# Power.net
KiCad netlist of a schematic drawn in Altium Designer
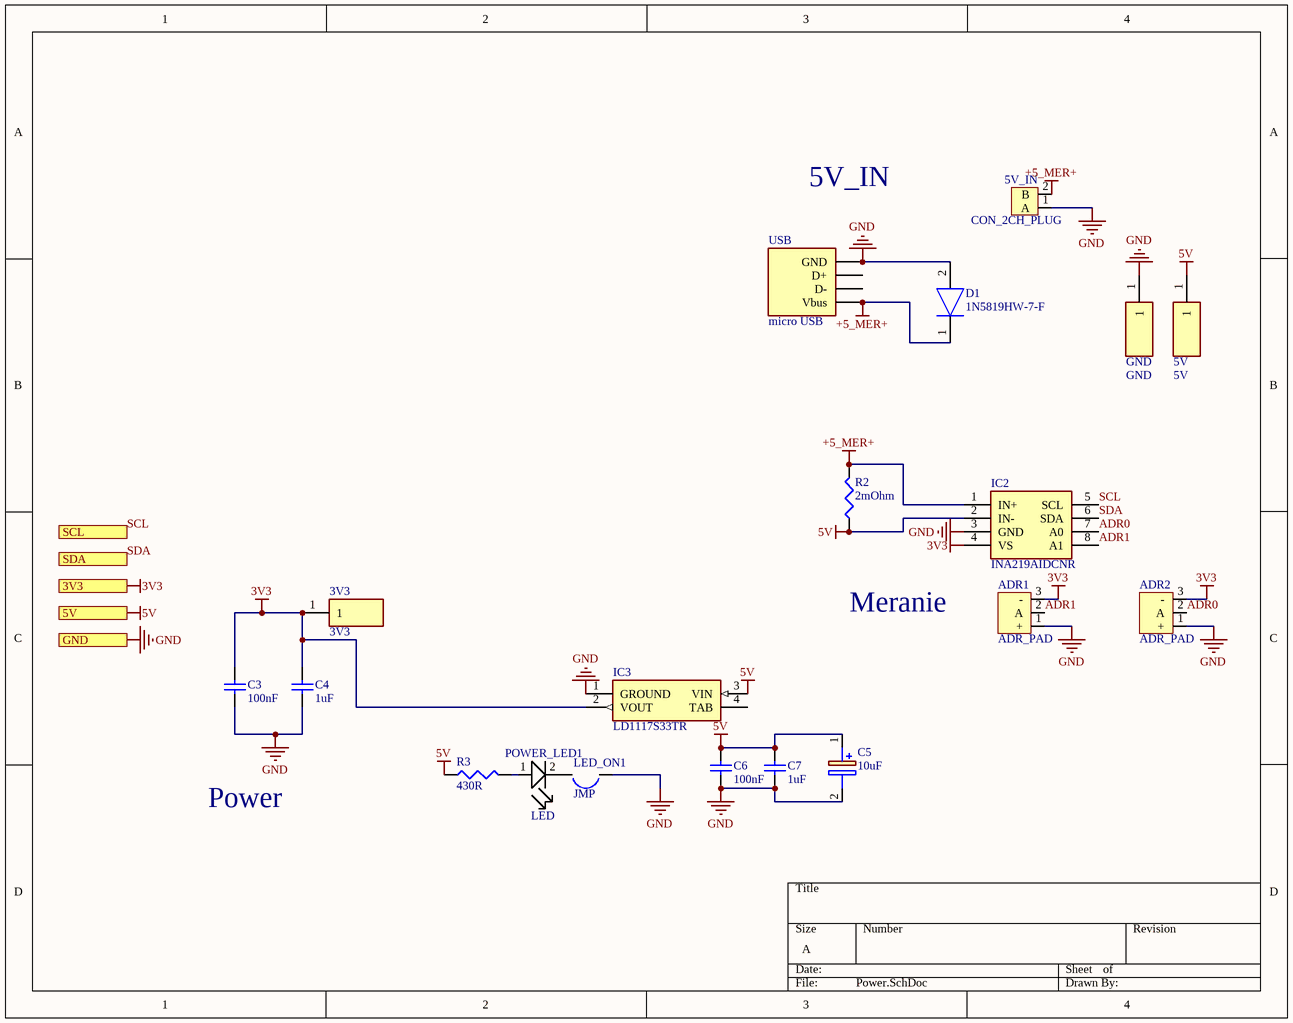
[diagram p0: Power.SchDoc]

(export (version "E")
  (design (tool "Eeschema 10.0.6"))
  (components
    (comp (ref "3V3")
      (value "3V3")
      (footprint "1508000150000030")
      (description "Undefined or Miscellaneous")
      (fields (field (name "MANUFACTURER_PART_NUMBER") "5015") (field (name "MOUSER PART NUMBER") "534-5015"))
      (libsource (lib "*") (part "5015"))
    )
    (comp (ref "5V")
      (value "5V")
      (footprint "1508000150000030")
      (description "Undefined or Miscellaneous")
      (fields (field (name "MANUFACTURER_PART_NUMBER") "5015") (field (name "MOUSER PART NUMBER") "534-5015"))
      (libsource (lib "") (part "5015_1"))
    )
    (comp (ref "5V_IN")
      (value "CON_2CH_PLUG")
      (footprint "CON_2CH_PLUG")
      (description "TBG-5.0-KW-2P")
      (libsource (lib "SCH_Aquatec") (part "CON_2CH_PLUG"))
    )
    (comp (ref "ADR1")
      (value "ADR_PAD")
      (footprint "SOLDER_PAD")
      (description "ADR PAD 3 PIN")
      (libsource (lib "SCH_Aquatec") (part "ADR_PAD"))
    )
    (comp (ref "ADR2")
      (value "ADR_PAD")
      (footprint "SOLDER_PAD")
      (description "ADR PAD 3 PIN")
      (libsource (lib "SCH_Aquatec") (part "ADR_PAD"))
    )
    (comp (ref "C3")
      (value "100nF")
      (footprint "1608[0603]")
      (description "Capacitor")
      (fields (field (name "PUBLISHER") "Altium Limited"))
      (libsource (lib "Miscellaneous Devices") (part "Cap Semi"))
    )
    (comp (ref "C4")
      (value "1uF")
      (footprint "1608[0603]")
      (description "Capacitor")
      (fields (field (name "PUBLISHER") "Altium Limited"))
      (libsource (lib "Miscellaneous Devices") (part "Cap Semi"))
    )
    (comp (ref "C5")
      (value "10uF")
      (footprint "CAPPM3216X180N")
      (description "Capacitor Polarised")
      (fields
        (field (name "MANUFACTURER_PART_NUMBER") "TAJA106K004RNJ")
        (field (name "MOUSER PART NUMBER") "581-TAJA106K004R")
      )
      (libsource (lib "*") (part "TAJA106K004RNJ"))
    )
    (comp (ref "C6")
      (value "100nF")
      (footprint "1608[0603]")
      (description "Capacitor")
      (fields (field (name "PUBLISHER") "Altium Limited"))
      (libsource (lib "Miscellaneous Devices") (part "Cap Semi"))
    )
    (comp (ref "C7")
      (value "1uF")
      (footprint "1608[0603]")
      (description "Capacitor")
      (fields (field (name "PUBLISHER") "Altium Limited"))
      (libsource (lib "Miscellaneous Devices") (part "Cap Semi"))
    )
    (comp (ref "D1")
      (value "1N5819HW-7-F")
      (footprint "SamacSys:SOD3716X145N")
      (description "Diode")
      (fields (field (name "MOUSER PART NUMBER") "621-1N5819HW-F"))
      (libsource (lib "*") (part "1N5819HW-7-F"))
    )
    (comp (ref "GND")
      (value "GND")
      (footprint "1508000150000030")
      (description "Undefined or Miscellaneous")
      (fields (field (name "MANUFACTURER_PART_NUMBER") "5015") (field (name "MOUSER PART NUMBER") "534-5015"))
      (libsource (lib "") (part "5015_1"))
    )
    (comp (ref "IC2")
      (value "INA219AIDCNR")
      (footprint "SOT65P280X145-8N")
      (description "Integrated Circuit")
      (fields
        (field (name "MANUFACTURER_PART_NUMBER") "INA219BIDCNR")
        (field (name "MOUSER PART NUMBER") "595-INA219BIDCNR")
      )
      (libsource (lib "*") (part "INA219BIDCNR"))
    )
    (comp (ref "IC3")
      (value "LD1117S33TR")
      (footprint "SOT230P700X180-4N")
      (description "Integrated Circuit")
      (fields (field (name "MOUSER PART NUMBER") "511-LD1117S33") (field (name "RS PART NUMBER") "7140697P"))
      (libsource (lib "*") (part "LD1117S33TR"))
    )
    (comp (ref "LED_ON1") (value "JMP") (footprint "JMP") (libsource (lib "SamacSys") (part "JMP")))
    (comp (ref "POWER_LED1")
      (value "LED")
      (footprint "LED5mA")
      (libsource (lib "SchematicLib_JP") (part "LED"))
    )
    (comp (ref "R2")
      (value "2mOhm")
      (footprint "RESC3216X75N")
      (description "Resistor")
      (fields (field (name "PUBLISHER") "Altium Limited"))
      (libsource (lib "Miscellaneous Devices") (part "Res3"))
    )
    (comp (ref "R3")
      (value "430R")
      (footprint "J1-0603")
      (description "Resistor")
      (fields (field (name "PUBLISHER") "Altium Limited"))
      (libsource (lib "Miscellaneous Devices") (part "Res3"))
    )
    (comp (ref "USB")
      (value "micro USB")
      (footprint "micro USB")
      (libsource (lib "SamacSys") (part "micro USB"))
    )
  )
  (nets
    (net (code "1") (name "+5_MER+") (class "Default")
      (node (ref "5V_IN") (pin "2") (pinfunction "B_2") (pintype "passive"))
      (node (ref "D1") (pin "1") (pinfunction "K_1") (pintype "passive"))
      (node (ref "IC2") (pin "1") (pinfunction "IN+_1") (pintype "passive"))
      (node (ref "R2") (pin "2") (pinfunction "2_2") (pintype "passive"))
      (node (ref "USB") (pin "1") (pinfunction "Vbus_1") (pintype "passive"))
    )
    (net (code "2") (name "/ADR0") (class "Default")
      (node (ref "ADR2") (pin "2") (pinfunction "A_2") (pintype "passive"))
      (node (ref "IC2") (pin "7") (pinfunction "A0_7") (pintype "passive"))
    )
    (net (code "3") (name "/ADR1") (class "Default")
      (node (ref "ADR1") (pin "2") (pinfunction "A_2") (pintype "passive"))
      (node (ref "IC2") (pin "8") (pinfunction "A1_8") (pintype "passive"))
    )
    (net (code "4") (name "/SCL") (class "Default")
      (node (ref "IC2") (pin "5") (pinfunction "SCL_5") (pintype "passive"))
    )
    (net (code "5") (name "/SDA") (class "Default")
      (node (ref "IC2") (pin "6") (pinfunction "SDA_6") (pintype "passive"))
    )
    (net (code "6") (name "3V3") (class "Default")
      (node (ref "3V3") (pin "1") (pinfunction "1_1") (pintype "passive"))
      (node (ref "ADR1") (pin "3") (pinfunction "-_3") (pintype "passive"))
      (node (ref "ADR2") (pin "3") (pinfunction "-_3") (pintype "passive"))
      (node (ref "C3") (pin "1") (pinfunction "1_1") (pintype "passive"))
      (node (ref "C4") (pin "1") (pinfunction "1_1") (pintype "passive"))
      (node (ref "IC2") (pin "4") (pinfunction "VS_4") (pintype "power_in"))
      (node (ref "IC3") (pin "2") (pinfunction "VOUT_2") (pintype "output"))
    )
    (net (code "7") (name "5V") (class "Default")
      (node (ref "5V") (pin "1") (pinfunction "1_1") (pintype "passive"))
      (node (ref "C5") (pin "1") (pinfunction "+_1") (pintype "passive"))
      (node (ref "C6") (pin "1") (pinfunction "1_1") (pintype "passive"))
      (node (ref "C7") (pin "1") (pinfunction "1_1") (pintype "passive"))
      (node (ref "IC2") (pin "2") (pinfunction "IN-_2") (pintype "passive"))
      (node (ref "IC3") (pin "3") (pinfunction "VIN_3") (pintype "input"))
      (node (ref "R2") (pin "1") (pinfunction "1_1") (pintype "passive"))
      (node (ref "R3") (pin "1") (pinfunction "1_1") (pintype "passive"))
    )
    (net (code "8") (name "GND") (class "Default")
      (node (ref "5V_IN") (pin "1") (pinfunction "A_1") (pintype "passive"))
      (node (ref "ADR1") (pin "1") (pinfunction "+_1") (pintype "passive"))
      (node (ref "ADR2") (pin "1") (pinfunction "+_1") (pintype "passive"))
      (node (ref "C3") (pin "2") (pinfunction "2_2") (pintype "passive"))
      (node (ref "C4") (pin "2") (pinfunction "2_2") (pintype "passive"))
      (node (ref "C5") (pin "2") (pinfunction "-_2") (pintype "passive"))
      (node (ref "C6") (pin "2") (pinfunction "2_2") (pintype "passive"))
      (node (ref "C7") (pin "2") (pinfunction "2_2") (pintype "passive"))
      (node (ref "D1") (pin "2") (pinfunction "A_2") (pintype "passive"))
      (node (ref "GND") (pin "1") (pinfunction "1_1") (pintype "passive"))
      (node (ref "IC2") (pin "3") (pinfunction "GND_3") (pintype "power_in"))
      (node (ref "IC3") (pin "1") (pinfunction "GROUND_1") (pintype "passive"))
      (node (ref "LED_ON1") (pin "1") (pinfunction "1_1") (pintype "passive"))
      (node (ref "USB") (pin "5") (pinfunction "GND_5") (pintype "passive"))
    )
    (net (code "9") (name "Net-(LED_ON1-Pad2)") (class "Default")
      (node (ref "LED_ON1") (pin "2") (pinfunction "2_2") (pintype "passive"))
      (node (ref "POWER_LED1") (pin "2") (pinfunction "2_2") (pintype "passive"))
    )
    (net (code "10") (name "Net-(POWER_LED1-Pad1)") (class "Default")
      (node (ref "POWER_LED1") (pin "1") (pinfunction "1_1") (pintype "passive"))
      (node (ref "R3") (pin "2") (pinfunction "2_2") (pintype "passive"))
    )
    (net (code "11") (name "unconnected-(IC3-TAB-Pad4)") (class "Default")
      (node (ref "IC3") (pin "4") (pinfunction "TAB_4") (pintype "passive"))
    )
    (net (code "12") (name "unconnected-(USB-D+-Pad3)") (class "Default")
      (node (ref "USB") (pin "3") (pinfunction "D+_3") (pintype "passive"))
    )
    (net (code "13") (name "unconnected-(USB-D--Pad2)") (class "Default")
      (node (ref "USB") (pin "2") (pinfunction "D-_2") (pintype "passive"))
    )
  )
)
